# Rajesh_Jasti_17978253_Lab1.net
KiCad netlist of a schematic drawn in Altium Designer
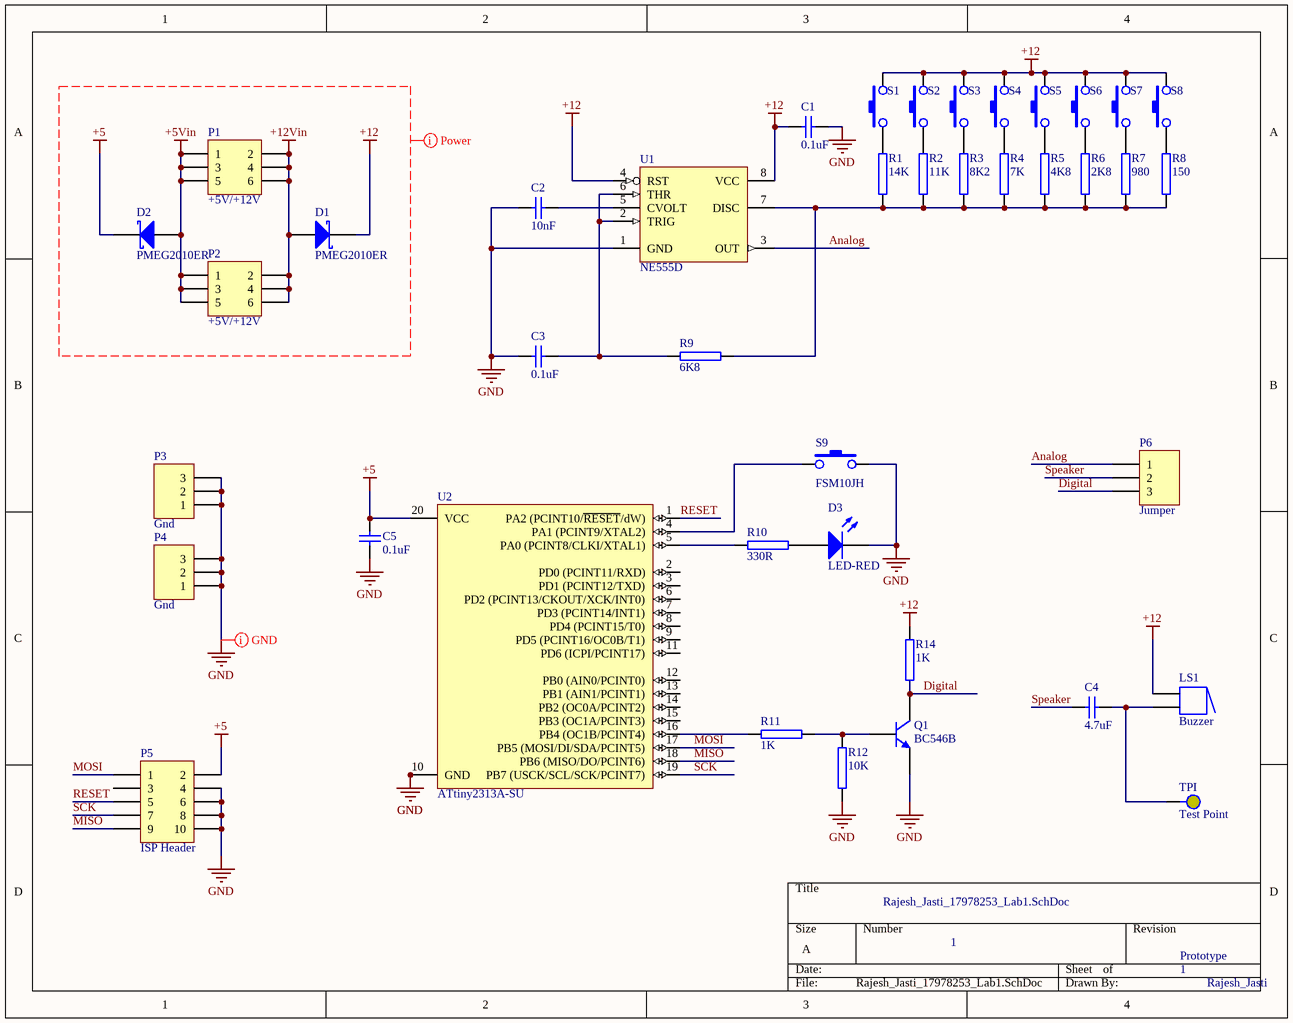
[diagram p0: Rajesh_Jasti_17978253_Lab1.SchDoc]

(export (version "E")
  (design (tool "Eeschema 10.0.6"))
  (components
    (comp (ref "C1")
      (value "0.1uF")
      (footprint "CAP_1206")
      (description "Non Polarized Capacitor, SMD, 1206")
      (libsource (lib "Resistors and Capacitors") (part "CAPN 1206"))
    )
    (comp (ref "C2")
      (value "10nF")
      (footprint "CAP_1206")
      (description "Non Polarized Capacitor, SMD, 1206")
      (libsource (lib "Resistors and Capacitors") (part "CAPN 1206"))
    )
    (comp (ref "C3")
      (value "0.1uF")
      (footprint "CAP_1206")
      (description "Non Polarized Capacitor, SMD, 1206")
      (libsource (lib "Resistors and Capacitors") (part "CAPN 1206"))
    )
    (comp (ref "C4")
      (value "4.7uF")
      (footprint "CAP_1206")
      (description "Non Polarized Capacitor, SMD, 1206")
      (libsource (lib "Resistors and Capacitors") (part "CAPN 1206"))
    )
    (comp (ref "C5")
      (value "0.1uF")
      (footprint "CAP_1206")
      (description "Non Polarized Capacitor, SMD, 1206")
      (libsource (lib "Resistors and Capacitors") (part "CAPN 1206"))
    )
    (comp (ref "D1")
      (value "PMEG2010ER")
      (footprint "SOD123W")
      (description "Schottky REC, 20V, 1A, 340mV, SMD SOD123W")
      (libsource (lib "Projects_2019") (part "PMEG2010ER"))
    )
    (comp (ref "D2")
      (value "PMEG2010ER")
      (footprint "SOD123W")
      (description "Schottky REC, 20V, 1A, 340mV, SMD SOD123W")
      (libsource (lib "Projects_2019") (part "PMEG2010ER"))
    )
    (comp (ref "D3")
      (value "LED-RED")
      (footprint "LED1206R")
      (description "RED LED, Case 1206")
      (libsource (lib "LEDs") (part "SMD 1206 LED-RED"))
    )
    (comp (ref "LS1")
      (value "Buzzer")
      (footprint "Buzzer")
      (description "Magnetic Transducer Buzzer")
      (libsource (lib "Projects_2016") (part "Buzzer"))
    )
    (comp (ref "P1")
      (value "+5V/+12V")
      (footprint "HDR2X3_AUT")
      (description "Header, 3-Pin, Dual row, 2.54mm Pitch, Straight")
      (libsource (lib "Connectors") (part "HDR3X2"))
    )
    (comp (ref "P2")
      (value "+5V/+12V")
      (footprint "HDR2X3_AUT")
      (description "Header, 3-Pin, Dual row, 2.54mm Pitch, Straight")
      (libsource (lib "Connectors") (part "HDR3X2"))
    )
    (comp (ref "P3")
      (value "Gnd")
      (footprint "HDR1X3_AUT")
      (description "Header, Plug, 2.54mm, 3 Pins, Straight")
      (libsource (lib "Connectors") (part "HDR1X3V"))
    )
    (comp (ref "P4")
      (value "Gnd")
      (footprint "HDR1X3_AUT")
      (description "Header, Plug, 2.54mm, 3 Pins, Straight")
      (libsource (lib "Connectors") (part "HDR1X3V"))
    )
    (comp (ref "P5")
      (value "ISP Header")
      (footprint "FKV10SN_AUT")
      (description "Header, Box, 10 Way, 2.54mm, Straght")
      (libsource (lib "Connectors") (part "Box Header 5X2/S"))
    )
    (comp (ref "P6")
      (value "Jumper")
      (footprint "HDR1X3_AUT")
      (description "Header, Plug, 2.54mm, 3 Pins, Straight")
      (libsource (lib "") (part "HDR1X3V_1"))
    )
    (comp (ref "Q1")
      (value "BC546B")
      (footprint "TO-92AUT")
      (description "NPN Bipolar Transistor; 65V, 100mA")
      (libsource (lib "Transistors and FETs") (part "BC546B"))
    )
    (comp (ref "R1")
      (value "14K")
      (footprint "AXIAL-0.3AUT")
      (description "Resistor, Through Hole, Pitch 300mil")
      (libsource (lib "Resistors and Capacitors") (part "Resistor 1/8W"))
    )
    (comp (ref "R2")
      (value "11K")
      (footprint "AXIAL-0.3AUT")
      (description "Resistor, Through Hole, Pitch 300mil")
      (libsource (lib "Resistors and Capacitors") (part "Resistor 1/8W"))
    )
    (comp (ref "R3")
      (value "8K2")
      (footprint "AXIAL-0.3AUT")
      (description "Resistor, Through Hole, Pitch 300mil")
      (libsource (lib "Resistors and Capacitors") (part "Resistor 1/8W"))
    )
    (comp (ref "R4")
      (value "7K")
      (footprint "AXIAL-0.3AUT")
      (description "Resistor, Through Hole, Pitch 300mil")
      (libsource (lib "Resistors and Capacitors") (part "Resistor 1/8W"))
    )
    (comp (ref "R5")
      (value "4K8")
      (footprint "AXIAL-0.3AUT")
      (description "Resistor, Through Hole, Pitch 300mil")
      (libsource (lib "Resistors and Capacitors") (part "Resistor 1/8W"))
    )
    (comp (ref "R6")
      (value "2K8")
      (footprint "AXIAL-0.3AUT")
      (description "Resistor, Through Hole, Pitch 300mil")
      (libsource (lib "Resistors and Capacitors") (part "Resistor 1/8W"))
    )
    (comp (ref "R7")
      (value "980")
      (footprint "AXIAL-0.3AUT")
      (description "Resistor, Through Hole, Pitch 300mil")
      (libsource (lib "Resistors and Capacitors") (part "Resistor 1/8W"))
    )
    (comp (ref "R8")
      (value "150")
      (footprint "AXIAL-0.3AUT")
      (description "Resistor, Through Hole, Pitch 300mil")
      (libsource (lib "Resistors and Capacitors") (part "Resistor 1/8W"))
    )
    (comp (ref "R9")
      (value "6K8")
      (footprint "AXIAL-0.3AUT")
      (description "Resistor, Through Hole, Pitch 300mil")
      (libsource (lib "Resistors and Capacitors") (part "Resistor 1/8W"))
    )
    (comp (ref "R10")
      (value "330R")
      (footprint "AXIAL-0.3AUT")
      (description "Resistor, Through Hole, Pitch 300mil")
      (libsource (lib "Resistors and Capacitors") (part "Resistor 1/8W"))
    )
    (comp (ref "R11")
      (value "1K")
      (footprint "AXIAL-0.3AUT")
      (description "Resistor, Through Hole, Pitch 300mil")
      (libsource (lib "Resistors and Capacitors") (part "Resistor 1/8W"))
    )
    (comp (ref "R12")
      (value "10K")
      (footprint "AXIAL-0.3AUT")
      (description "Resistor, Through Hole, Pitch 300mil")
      (libsource (lib "Resistors and Capacitors") (part "Resistor 1/8W"))
    )
    (comp (ref "R14")
      (value "1K")
      (footprint "AXIAL-0.3AUT")
      (description "Resistor, Through Hole, Pitch 300mil")
      (libsource (lib "Resistors and Capacitors") (part "Resistor 1/8W"))
    )
    (comp (ref "S1")
      (value "FSM10JH")
      (footprint "FSM10JH")
      (description "Switch, SPST, 0.05A, 12VDC")
      (libsource (lib "Switches") (part "FSM10JH"))
    )
    (comp (ref "S2")
      (value "FSM10JH")
      (footprint "FSM10JH")
      (description "Switch, SPST, 0.05A, 12VDC")
      (libsource (lib "Switches") (part "FSM10JH"))
    )
    (comp (ref "S3")
      (value "FSM10JH")
      (footprint "FSM10JH")
      (description "Switch, SPST, 0.05A, 12VDC")
      (libsource (lib "Switches") (part "FSM10JH"))
    )
    (comp (ref "S4")
      (value "FSM10JH")
      (footprint "FSM10JH")
      (description "Switch, SPST, 0.05A, 12VDC")
      (libsource (lib "Switches") (part "FSM10JH"))
    )
    (comp (ref "S5")
      (value "FSM10JH")
      (footprint "FSM10JH")
      (description "Switch, SPST, 0.05A, 12VDC")
      (libsource (lib "Switches") (part "FSM10JH"))
    )
    (comp (ref "S6")
      (value "FSM10JH")
      (footprint "FSM10JH")
      (description "Switch, SPST, 0.05A, 12VDC")
      (libsource (lib "Switches") (part "FSM10JH"))
    )
    (comp (ref "S7")
      (value "FSM10JH")
      (footprint "FSM10JH")
      (description "Switch, SPST, 0.05A, 12VDC")
      (libsource (lib "Switches") (part "FSM10JH"))
    )
    (comp (ref "S8")
      (value "FSM10JH")
      (footprint "FSM10JH")
      (description "Switch, SPST, 0.05A, 12VDC")
      (libsource (lib "Switches") (part "FSM10JH"))
    )
    (comp (ref "S9")
      (value "FSM10JH")
      (footprint "FSM10JH")
      (description "Switch, SPST, 0.05A, 12VDC")
      (libsource (lib "Switches") (part "FSM10JH"))
    )
    (comp (ref "TPI")
      (value "Test Point")
      (footprint "PAD1_AUT")
      (description "Terminal, Pad 70x70mil, Hole 32 mil")
      (libsource (lib "Connectors") (part "Terminal1"))
    )
    (comp (ref "U1")
      (value "NE555D")
      (footprint "SO8_M")
      (description "General-Purpose Single Bipolar Timer, SMD")
      (libsource (lib "Interface and Driver_old") (part "NE555D"))
    )
    (comp (ref "U2")
      (value "ATtiny2313A-SU")
      (footprint "20S_M")
      (description "8-bit AVR Microcontroller, 1.8-5.5V, 2KB Flash, 128 Bytes EEPROM, 128 Bytes SRAM")
      (libsource (lib "Atmel_Tiny_Micro") (part "ATtiny2313A-SU"))
    )
  )
  (nets
    (net (code "1") (name "+5") (class "Default")
      (node (ref "C5") (pin "2") (pinfunction "2_2") (pintype "passive"))
      (node (ref "D2") (pin "1") (pinfunction "K_1") (pintype "passive"))
      (node (ref "P5") (pin "2") (pinfunction "2_2") (pintype "passive"))
      (node (ref "U2") (pin "20") (pinfunction "VCC_20") (pintype "power_in"))
    )
    (net (code "2") (name "+5Vin") (class "Default")
      (node (ref "D2") (pin "2") (pinfunction "A_2") (pintype "passive"))
      (node (ref "P1") (pin "1") (pinfunction "1_1") (pintype "passive"))
      (node (ref "P1") (pin "3") (pinfunction "3_3") (pintype "passive"))
      (node (ref "P1") (pin "5") (pinfunction "5_5") (pintype "passive"))
      (node (ref "P2") (pin "1") (pinfunction "1_1") (pintype "passive"))
      (node (ref "P2") (pin "3") (pinfunction "3_3") (pintype "passive"))
      (node (ref "P2") (pin "5") (pinfunction "5_5") (pintype "passive"))
    )
    (net (code "3") (name "+12") (class "Default")
      (node (ref "C1") (pin "1") (pinfunction "1_1") (pintype "passive"))
      (node (ref "D1") (pin "1") (pinfunction "K_1") (pintype "passive"))
      (node (ref "LS1") (pin "1") (pinfunction "1_1") (pintype "passive"))
      (node (ref "R14") (pin "2") (pinfunction "2_2") (pintype "passive"))
      (node (ref "S1") (pin "2") (pinfunction "2_2") (pintype "passive"))
      (node (ref "S2") (pin "2") (pinfunction "2_2") (pintype "passive"))
      (node (ref "S3") (pin "2") (pinfunction "2_2") (pintype "passive"))
      (node (ref "S4") (pin "2") (pinfunction "2_2") (pintype "passive"))
      (node (ref "S5") (pin "2") (pinfunction "2_2") (pintype "passive"))
      (node (ref "S6") (pin "2") (pinfunction "2_2") (pintype "passive"))
      (node (ref "S7") (pin "2") (pinfunction "2_2") (pintype "passive"))
      (node (ref "S8") (pin "2") (pinfunction "2_2") (pintype "passive"))
      (node (ref "U1") (pin "4") (pinfunction "RST_4") (pintype "input"))
      (node (ref "U1") (pin "8") (pinfunction "VCC_8") (pintype "power_in"))
    )
    (net (code "4") (name "+12Vin") (class "Default")
      (node (ref "D1") (pin "2") (pinfunction "A_2") (pintype "passive"))
      (node (ref "P1") (pin "2") (pinfunction "2_2") (pintype "passive"))
      (node (ref "P1") (pin "4") (pinfunction "4_4") (pintype "passive"))
      (node (ref "P1") (pin "6") (pinfunction "6_6") (pintype "passive"))
      (node (ref "P2") (pin "2") (pinfunction "2_2") (pintype "passive"))
      (node (ref "P2") (pin "4") (pinfunction "4_4") (pintype "passive"))
      (node (ref "P2") (pin "6") (pinfunction "6_6") (pintype "passive"))
    )
    (net (code "5") (name "/Analog") (class "Default")
      (node (ref "P6") (pin "1") (pinfunction "1_1") (pintype "passive"))
      (node (ref "U1") (pin "3") (pinfunction "OUT_3") (pintype "output"))
    )
    (net (code "6") (name "/Digital") (class "Default")
      (node (ref "P6") (pin "3") (pinfunction "3_3") (pintype "passive"))
      (node (ref "Q1") (pin "1") (pinfunction "C_1") (pintype "passive"))
      (node (ref "R14") (pin "1") (pinfunction "1_1") (pintype "passive"))
    )
    (net (code "7") (name "/MISO") (class "Default")
      (node (ref "P5") (pin "9") (pinfunction "9_9") (pintype "passive"))
      (node (ref "U2") (pin "18") (pinfunction "PB6_(MISO/DO/PCINT6)_18") (pintype "bidirectional"))
    )
    (net (code "8") (name "/MOSI") (class "Default")
      (node (ref "P5") (pin "1") (pinfunction "1_1") (pintype "passive"))
      (node (ref "U2") (pin "17") (pinfunction "PB5_(MOSI/DI/SDA/PCINT5)_17") (pintype "bidirectional"))
    )
    (net (code "9") (name "/RESET") (class "Default")
      (node (ref "P5") (pin "5") (pinfunction "5_5") (pintype "passive"))
      (node (ref "U2") (pin "1") (pinfunction "PA2_(PCINT10/~{RESET}/dW)_1") (pintype "bidirectional"))
    )
    (net (code "10") (name "/SCK") (class "Default")
      (node (ref "P5") (pin "7") (pinfunction "7_7") (pintype "passive"))
      (node (ref "U2") (pin "19") (pinfunction "PB7_(USCK/SCL/SCK/PCINT7)_19") (pintype "bidirectional"))
    )
    (net (code "11") (name "/Speaker") (class "Default")
      (node (ref "C4") (pin "1") (pinfunction "1_1") (pintype "passive"))
      (node (ref "P6") (pin "2") (pinfunction "2_2") (pintype "passive"))
    )
    (net (code "12") (name "GND") (class "Default")
      (node (ref "C1") (pin "2") (pinfunction "2_2") (pintype "passive"))
      (node (ref "C2") (pin "1") (pinfunction "1_1") (pintype "passive"))
      (node (ref "C3") (pin "1") (pinfunction "1_1") (pintype "passive"))
      (node (ref "C5") (pin "1") (pinfunction "1_1") (pintype "passive"))
      (node (ref "D3") (pin "K") (pinfunction "K_K") (pintype "passive"))
      (node (ref "P3") (pin "1") (pinfunction "1_1") (pintype "passive"))
      (node (ref "P3") (pin "2") (pinfunction "2_2") (pintype "passive"))
      (node (ref "P3") (pin "3") (pinfunction "3_3") (pintype "passive"))
      (node (ref "P4") (pin "1") (pinfunction "1_1") (pintype "passive"))
      (node (ref "P4") (pin "2") (pinfunction "2_2") (pintype "passive"))
      (node (ref "P4") (pin "3") (pinfunction "3_3") (pintype "passive"))
      (node (ref "P5") (pin "10") (pinfunction "10_10") (pintype "passive"))
      (node (ref "P5") (pin "4") (pinfunction "4_4") (pintype "passive"))
      (node (ref "P5") (pin "6") (pinfunction "6_6") (pintype "passive"))
      (node (ref "P5") (pin "8") (pinfunction "8_8") (pintype "passive"))
      (node (ref "Q1") (pin "3") (pinfunction "E_3") (pintype "passive"))
      (node (ref "R12") (pin "1") (pinfunction "1_1") (pintype "passive"))
      (node (ref "S9") (pin "2") (pinfunction "2_2") (pintype "passive"))
      (node (ref "U1") (pin "1") (pinfunction "GND_1") (pintype "power_in"))
      (node (ref "U2") (pin "10") (pinfunction "GND_10") (pintype "power_in"))
    )
    (net (code "13") (name "Net-(C4-Pad2)") (class "Default")
      (node (ref "C4") (pin "2") (pinfunction "2_2") (pintype "passive"))
      (node (ref "LS1") (pin "2") (pinfunction "2_2") (pintype "passive"))
      (node (ref "TPI") (pin "1") (pintype "passive"))
    )
    (net (code "14") (name "Net-(D3-PadA)") (class "Default")
      (node (ref "D3") (pin "A") (pinfunction "A_A") (pintype "passive"))
      (node (ref "R10") (pin "1") (pinfunction "1_1") (pintype "passive"))
    )
    (net (code "15") (name "Net-(Q1-B)") (class "Default")
      (node (ref "Q1") (pin "2") (pinfunction "B_2") (pintype "passive"))
      (node (ref "R11") (pin "1") (pinfunction "1_1") (pintype "passive"))
      (node (ref "R12") (pin "2") (pinfunction "2_2") (pintype "passive"))
    )
    (net (code "16") (name "Net-(R1-Pad2)") (class "Default")
      (node (ref "R1") (pin "2") (pinfunction "2_2") (pintype "passive"))
      (node (ref "S1") (pin "1") (pinfunction "1_1") (pintype "passive"))
    )
    (net (code "17") (name "Net-(R2-Pad2)") (class "Default")
      (node (ref "R2") (pin "2") (pinfunction "2_2") (pintype "passive"))
      (node (ref "S2") (pin "1") (pinfunction "1_1") (pintype "passive"))
    )
    (net (code "18") (name "Net-(R3-Pad2)") (class "Default")
      (node (ref "R3") (pin "2") (pinfunction "2_2") (pintype "passive"))
      (node (ref "S3") (pin "1") (pinfunction "1_1") (pintype "passive"))
    )
    (net (code "19") (name "Net-(R4-Pad2)") (class "Default")
      (node (ref "R4") (pin "2") (pinfunction "2_2") (pintype "passive"))
      (node (ref "S4") (pin "1") (pinfunction "1_1") (pintype "passive"))
    )
    (net (code "20") (name "Net-(R5-Pad2)") (class "Default")
      (node (ref "R5") (pin "2") (pinfunction "2_2") (pintype "passive"))
      (node (ref "S5") (pin "1") (pinfunction "1_1") (pintype "passive"))
    )
    (net (code "21") (name "Net-(R6-Pad2)") (class "Default")
      (node (ref "R6") (pin "2") (pinfunction "2_2") (pintype "passive"))
      (node (ref "S6") (pin "1") (pinfunction "1_1") (pintype "passive"))
    )
    (net (code "22") (name "Net-(R7-Pad2)") (class "Default")
      (node (ref "R7") (pin "2") (pinfunction "2_2") (pintype "passive"))
      (node (ref "S7") (pin "1") (pinfunction "1_1") (pintype "passive"))
    )
    (net (code "23") (name "Net-(R8-Pad2)") (class "Default")
      (node (ref "R8") (pin "2") (pinfunction "2_2") (pintype "passive"))
      (node (ref "S8") (pin "1") (pinfunction "1_1") (pintype "passive"))
    )
    (net (code "24") (name "Net-(U1-CVOLT)") (class "Default")
      (node (ref "C2") (pin "2") (pinfunction "2_2") (pintype "passive"))
      (node (ref "U1") (pin "5") (pinfunction "CVOLT_5") (pintype "passive"))
    )
    (net (code "25") (name "Net-(U1-DISC)") (class "Default")
      (node (ref "R1") (pin "1") (pinfunction "1_1") (pintype "passive"))
      (node (ref "R2") (pin "1") (pinfunction "1_1") (pintype "passive"))
      (node (ref "R3") (pin "1") (pinfunction "1_1") (pintype "passive"))
      (node (ref "R4") (pin "1") (pinfunction "1_1") (pintype "passive"))
      (node (ref "R5") (pin "1") (pinfunction "1_1") (pintype "passive"))
      (node (ref "R6") (pin "1") (pinfunction "1_1") (pintype "passive"))
      (node (ref "R7") (pin "1") (pinfunction "1_1") (pintype "passive"))
      (node (ref "R8") (pin "1") (pinfunction "1_1") (pintype "passive"))
      (node (ref "R9") (pin "1") (pinfunction "1_1") (pintype "passive"))
      (node (ref "U1") (pin "7") (pinfunction "DISC_7") (pintype "open_collector"))
    )
    (net (code "26") (name "Net-(U1-THR)") (class "Default")
      (node (ref "C3") (pin "2") (pinfunction "2_2") (pintype "passive"))
      (node (ref "R9") (pin "2") (pinfunction "2_2") (pintype "passive"))
      (node (ref "U1") (pin "2") (pinfunction "TRIG_2") (pintype "input"))
      (node (ref "U1") (pin "6") (pinfunction "THR_6") (pintype "input"))
    )
    (net (code "27") (name "Net-(U2-PA0_(PCINT8{slash}CLKI{slash}XTAL1))") (class "Default")
      (node (ref "R10") (pin "2") (pinfunction "2_2") (pintype "passive"))
      (node (ref "U2") (pin "5") (pinfunction "PA0_(PCINT8/CLKI/XTAL1)_5") (pintype "bidirectional"))
    )
    (net (code "28") (name "Net-(U2-PA1_(PCINT9{slash}XTAL2))") (class "Default")
      (node (ref "S9") (pin "1") (pinfunction "1_1") (pintype "passive"))
      (node (ref "U2") (pin "4") (pinfunction "PA1_(PCINT9/XTAL2)_4") (pintype "bidirectional"))
    )
    (net (code "29") (name "Net-(U2-PB4_(OC1B{slash}PCINT4))") (class "Default")
      (node (ref "R11") (pin "2") (pinfunction "2_2") (pintype "passive"))
      (node (ref "U2") (pin "16") (pinfunction "PB4_(OC1B/PCINT4)_16") (pintype "bidirectional"))
    )
    (net (code "30") (name "unconnected-(P5-Pad3)") (class "Default")
      (node (ref "P5") (pin "3") (pinfunction "3_3") (pintype "passive"))
    )
    (net (code "31") (name "unconnected-(U2-PB0_(AIN0{slash}PCINT0)-Pad12)") (class "Default")
      (node (ref "U2") (pin "12") (pinfunction "PB0_(AIN0/PCINT0)_12") (pintype "bidirectional"))
    )
    (net (code "32") (name "unconnected-(U2-PB1_(AIN1{slash}PCINT1)-Pad13)") (class "Default")
      (node (ref "U2") (pin "13") (pinfunction "PB1_(AIN1/PCINT1)_13") (pintype "bidirectional"))
    )
    (net (code "33") (name "unconnected-(U2-PB2_(OC0A{slash}PCINT2)-Pad14)") (class "Default")
      (node (ref "U2") (pin "14") (pinfunction "PB2_(OC0A/PCINT2)_14") (pintype "bidirectional"))
    )
    (net (code "34") (name "unconnected-(U2-PB3_(OC1A{slash}PCINT3)-Pad15)") (class "Default")
      (node (ref "U2") (pin "15") (pinfunction "PB3_(OC1A/PCINT3)_15") (pintype "bidirectional"))
    )
    (net (code "35") (name "unconnected-(U2-PD0_(PCINT11{slash}RXD)-Pad2)") (class "Default")
      (node (ref "U2") (pin "2") (pinfunction "PD0_(PCINT11/RXD)_2") (pintype "bidirectional"))
    )
    (net (code "36") (name "unconnected-(U2-PD1_(PCINT12{slash}TXD)-Pad3)") (class "Default")
      (node (ref "U2") (pin "3") (pinfunction "PD1_(PCINT12/TXD)_3") (pintype "bidirectional"))
    )
    (net (code "37") (name "unconnected-(U2-PD2_(PCINT13{slash}CKOUT{slash}XCK{slash}INT0)-Pad6)") (class "Default")
      (node (ref "U2") (pin "6") (pinfunction "PD2_(PCINT13/CKOUT/XCK/INT0)_6") (pintype "bidirectional"))
    )
    (net (code "38") (name "unconnected-(U2-PD3_(PCINT14{slash}INT1)-Pad7)") (class "Default")
      (node (ref "U2") (pin "7") (pinfunction "PD3_(PCINT14/INT1)_7") (pintype "bidirectional"))
    )
    (net (code "39") (name "unconnected-(U2-PD4_(PCINT15{slash}T0)-Pad8)") (class "Default")
      (node (ref "U2") (pin "8") (pinfunction "PD4_(PCINT15/T0)_8") (pintype "bidirectional"))
    )
    (net (code "40") (name "unconnected-(U2-PD5_(PCINT16{slash}OC0B{slash}T1)-Pad9)") (class "Default")
      (node (ref "U2") (pin "9") (pinfunction "PD5_(PCINT16/OC0B/T1)_9") (pintype "bidirectional"))
    )
    (net (code "41") (name "unconnected-(U2-PD6_(ICPI{slash}PCINT17)-Pad11)") (class "Default")
      (node (ref "U2") (pin "11") (pinfunction "PD6_(ICPI/PCINT17)_11") (pintype "bidirectional"))
    )
  )
)
